# Drive.net
KiCad netlist of a schematic drawn in Altium Designer
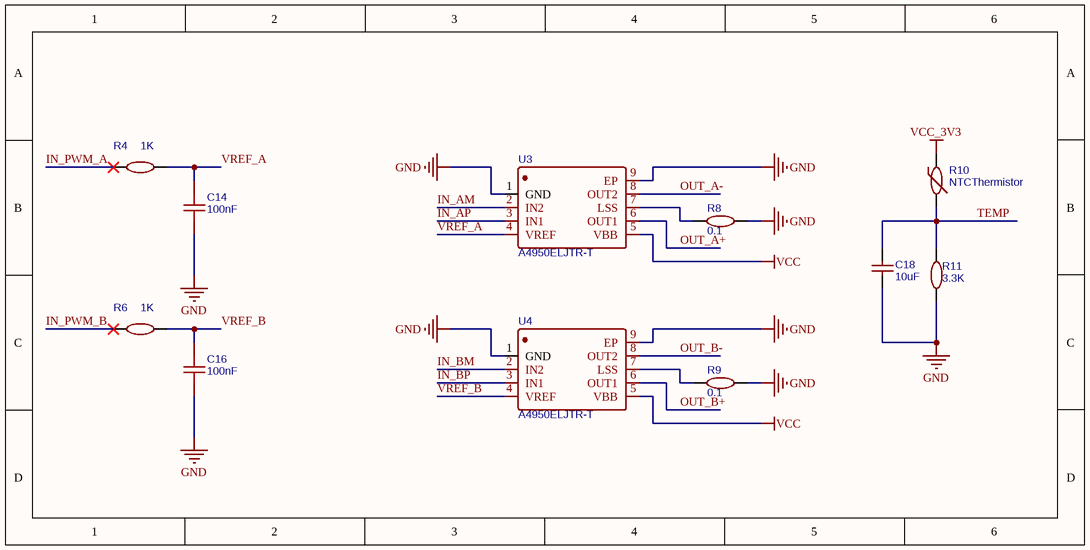
[diagram p0: Drive.SchDoc]

(export (version "E")
  (design (tool "Eeschema 10.0.6"))
  (components
    (comp (ref "C14")
      (value "100nF")
      (footprint "C0603")
      (fields
        (field (name "BOM_MANUFACTURER PART") "CL10B104KB8NNNC")
        (field (name "BOM_SUPPLIER PART") "C1591")
      )
      (libsource (lib "0.1uF") (part "100nF"))
    )
    (comp (ref "C16")
      (value "100nF")
      (footprint "C0603")
      (fields
        (field (name "BOM_MANUFACTURER PART") "CL10B104KB8NNNC")
        (field (name "BOM_SUPPLIER PART") "C1591")
      )
      (libsource (lib "0.1uF") (part "100nF"))
    )
    (comp (ref "C18")
      (value "10uF")
      (footprint "C1206")
      (fields
        (field (name "BOM_MANUFACTURER PART") "CL31A106KBHNNNE")
        (field (name "BOM_SUPPLIER PART") "C13585")
      )
      (libsource (lib "10uF") (part "10uF"))
    )
    (comp (ref "R4")
      (value "1K")
      (footprint "R0603")
      (fields
        (field (name "BOM_MANUFACTURER PART") "0603WAF1001T5E")
        (field (name "BOM_SUPPLIER PART") "C21190")
      )
      (libsource (lib "1K") (part "1K"))
    )
    (comp (ref "R6")
      (value "1K")
      (footprint "R0603")
      (fields
        (field (name "BOM_MANUFACTURER PART") "0603WAF1001T5E")
        (field (name "BOM_SUPPLIER PART") "C21190")
      )
      (libsource (lib "1K") (part "1K"))
    )
    (comp (ref "R8")
      (value "0.1")
      (footprint "R1206")
      (fields
        (field (name "BOM_MANUFACTURER PART") "1206W4F100LT5E")
        (field (name "BOM_SUPPLIER PART") "C25334")
      )
      (libsource (lib "0.1R") (part "0.1"))
    )
    (comp (ref "R9")
      (value "0.1")
      (footprint "R1206")
      (fields
        (field (name "BOM_MANUFACTURER PART") "1206W4F100LT5E")
        (field (name "BOM_SUPPLIER PART") "C25334")
      )
      (libsource (lib "0.1R") (part "0.1"))
    )
    (comp (ref "R10")
      (value "NTCThermistor")
      (footprint "R0402")
      (fields
        (field (name "BOM_MANUFACTURER PART") "NCP15XH103F03RC")
        (field (name "BOM_SUPPLIER PART") "C77131")
      )
      (libsource (lib "10K THERMISTOR") (part "NTCThermistor"))
    )
    (comp (ref "R11")
      (value "3.3K")
      (footprint "R0603_NEW")
      (fields
        (field (name "BOM_MANUFACTURER PART") "0603WAF3301T5E")
        (field (name "BOM_SUPPLIER PART") "C22978")
      )
      (libsource (lib "3.3K") (part "3.3K"))
    )
    (comp (ref "U3")
      (value "A4950ELJTR-T")
      (footprint "SOIC-8_L4.9-W3.9-P1.27-LS6.0-BL-EP")
      (fields (field (name "BOM_SUPPLIER PART") "C82404"))
      (libsource (lib "A4950") (part "A4950ELJTR-T"))
    )
    (comp (ref "U4")
      (value "A4950ELJTR-T")
      (footprint "SOIC-8_L4.9-W3.9-P1.27-LS6.0-BL-EP")
      (fields (field (name "BOM_SUPPLIER PART") "C82404"))
      (libsource (lib "A4950") (part "A4950ELJTR-T"))
    )
  )
  (nets
    (net (code "1") (name "/IN_AM") (class "Default")
      (node (ref "U3") (pin "2") (pinfunction "IN2_2") (pintype "passive"))
    )
    (net (code "2") (name "/IN_AP") (class "Default")
      (node (ref "U3") (pin "3") (pinfunction "IN1_3") (pintype "passive"))
    )
    (net (code "3") (name "/IN_BM") (class "Default")
      (node (ref "U4") (pin "2") (pinfunction "IN2_2") (pintype "passive"))
    )
    (net (code "4") (name "/IN_BP") (class "Default")
      (node (ref "U4") (pin "3") (pinfunction "IN1_3") (pintype "passive"))
    )
    (net (code "5") (name "/IN_PWM_A") (class "Default")
      (node (ref "R4") (pin "1") (pinfunction "1_1") (pintype "passive+no_connect"))
    )
    (net (code "6") (name "/IN_PWM_B") (class "Default")
      (node (ref "R6") (pin "1") (pinfunction "1_1") (pintype "passive+no_connect"))
    )
    (net (code "7") (name "/OUT_A+") (class "Default")
      (node (ref "U3") (pin "6") (pinfunction "OUT1_6") (pintype "passive"))
    )
    (net (code "8") (name "/OUT_A-") (class "Default")
      (node (ref "U3") (pin "8") (pinfunction "OUT2_8") (pintype "passive"))
    )
    (net (code "9") (name "/OUT_B+") (class "Default")
      (node (ref "U4") (pin "6") (pinfunction "OUT1_6") (pintype "passive"))
    )
    (net (code "10") (name "/OUT_B-") (class "Default")
      (node (ref "U4") (pin "8") (pinfunction "OUT2_8") (pintype "passive"))
    )
    (net (code "11") (name "/TEMP") (class "Default")
      (node (ref "C18") (pin "2") (pinfunction "2_2") (pintype "passive"))
      (node (ref "R10") (pin "2") (pinfunction "2_2") (pintype "passive"))
      (node (ref "R11") (pin "2") (pinfunction "2_2") (pintype "passive"))
    )
    (net (code "12") (name "/VREF_A") (class "Default")
      (node (ref "C14") (pin "2") (pinfunction "2_2") (pintype "passive"))
      (node (ref "R4") (pin "2") (pinfunction "2_2") (pintype "passive"))
      (node (ref "U3") (pin "4") (pinfunction "VREF_4") (pintype "passive"))
    )
    (net (code "13") (name "/VREF_B") (class "Default")
      (node (ref "C16") (pin "2") (pinfunction "2_2") (pintype "passive"))
      (node (ref "R6") (pin "2") (pinfunction "2_2") (pintype "passive"))
      (node (ref "U4") (pin "4") (pinfunction "VREF_4") (pintype "passive"))
    )
    (net (code "14") (name "GND") (class "Default")
      (node (ref "C14") (pin "1") (pinfunction "1_1") (pintype "passive"))
      (node (ref "C16") (pin "1") (pinfunction "1_1") (pintype "passive"))
      (node (ref "C18") (pin "1") (pinfunction "1_1") (pintype "passive"))
      (node (ref "R11") (pin "1") (pinfunction "1_1") (pintype "passive"))
      (node (ref "R8") (pin "2") (pinfunction "2_2") (pintype "passive"))
      (node (ref "R9") (pin "2") (pinfunction "2_2") (pintype "passive"))
      (node (ref "U3") (pin "1") (pinfunction "GND_1") (pintype "passive"))
      (node (ref "U3") (pin "9") (pinfunction "EP_9") (pintype "passive"))
      (node (ref "U4") (pin "1") (pinfunction "GND_1") (pintype "passive"))
      (node (ref "U4") (pin "9") (pinfunction "EP_9") (pintype "passive"))
    )
    (net (code "15") (name "Net-(U3-LSS)") (class "Default")
      (node (ref "R8") (pin "1") (pinfunction "1_1") (pintype "passive"))
      (node (ref "U3") (pin "7") (pinfunction "LSS_7") (pintype "passive"))
    )
    (net (code "16") (name "Net-(U4-LSS)") (class "Default")
      (node (ref "R9") (pin "1") (pinfunction "1_1") (pintype "passive"))
      (node (ref "U4") (pin "7") (pinfunction "LSS_7") (pintype "passive"))
    )
    (net (code "17") (name "VCC") (class "Default")
      (node (ref "U3") (pin "5") (pinfunction "VBB_5") (pintype "passive"))
      (node (ref "U4") (pin "5") (pinfunction "VBB_5") (pintype "passive"))
    )
    (net (code "18") (name "VCC_3V3") (class "Default")
      (node (ref "R10") (pin "1") (pinfunction "1_1") (pintype "passive"))
    )
  )
)
